# kbd.net
KiCad netlist of a schematic drawn in Altium Designer
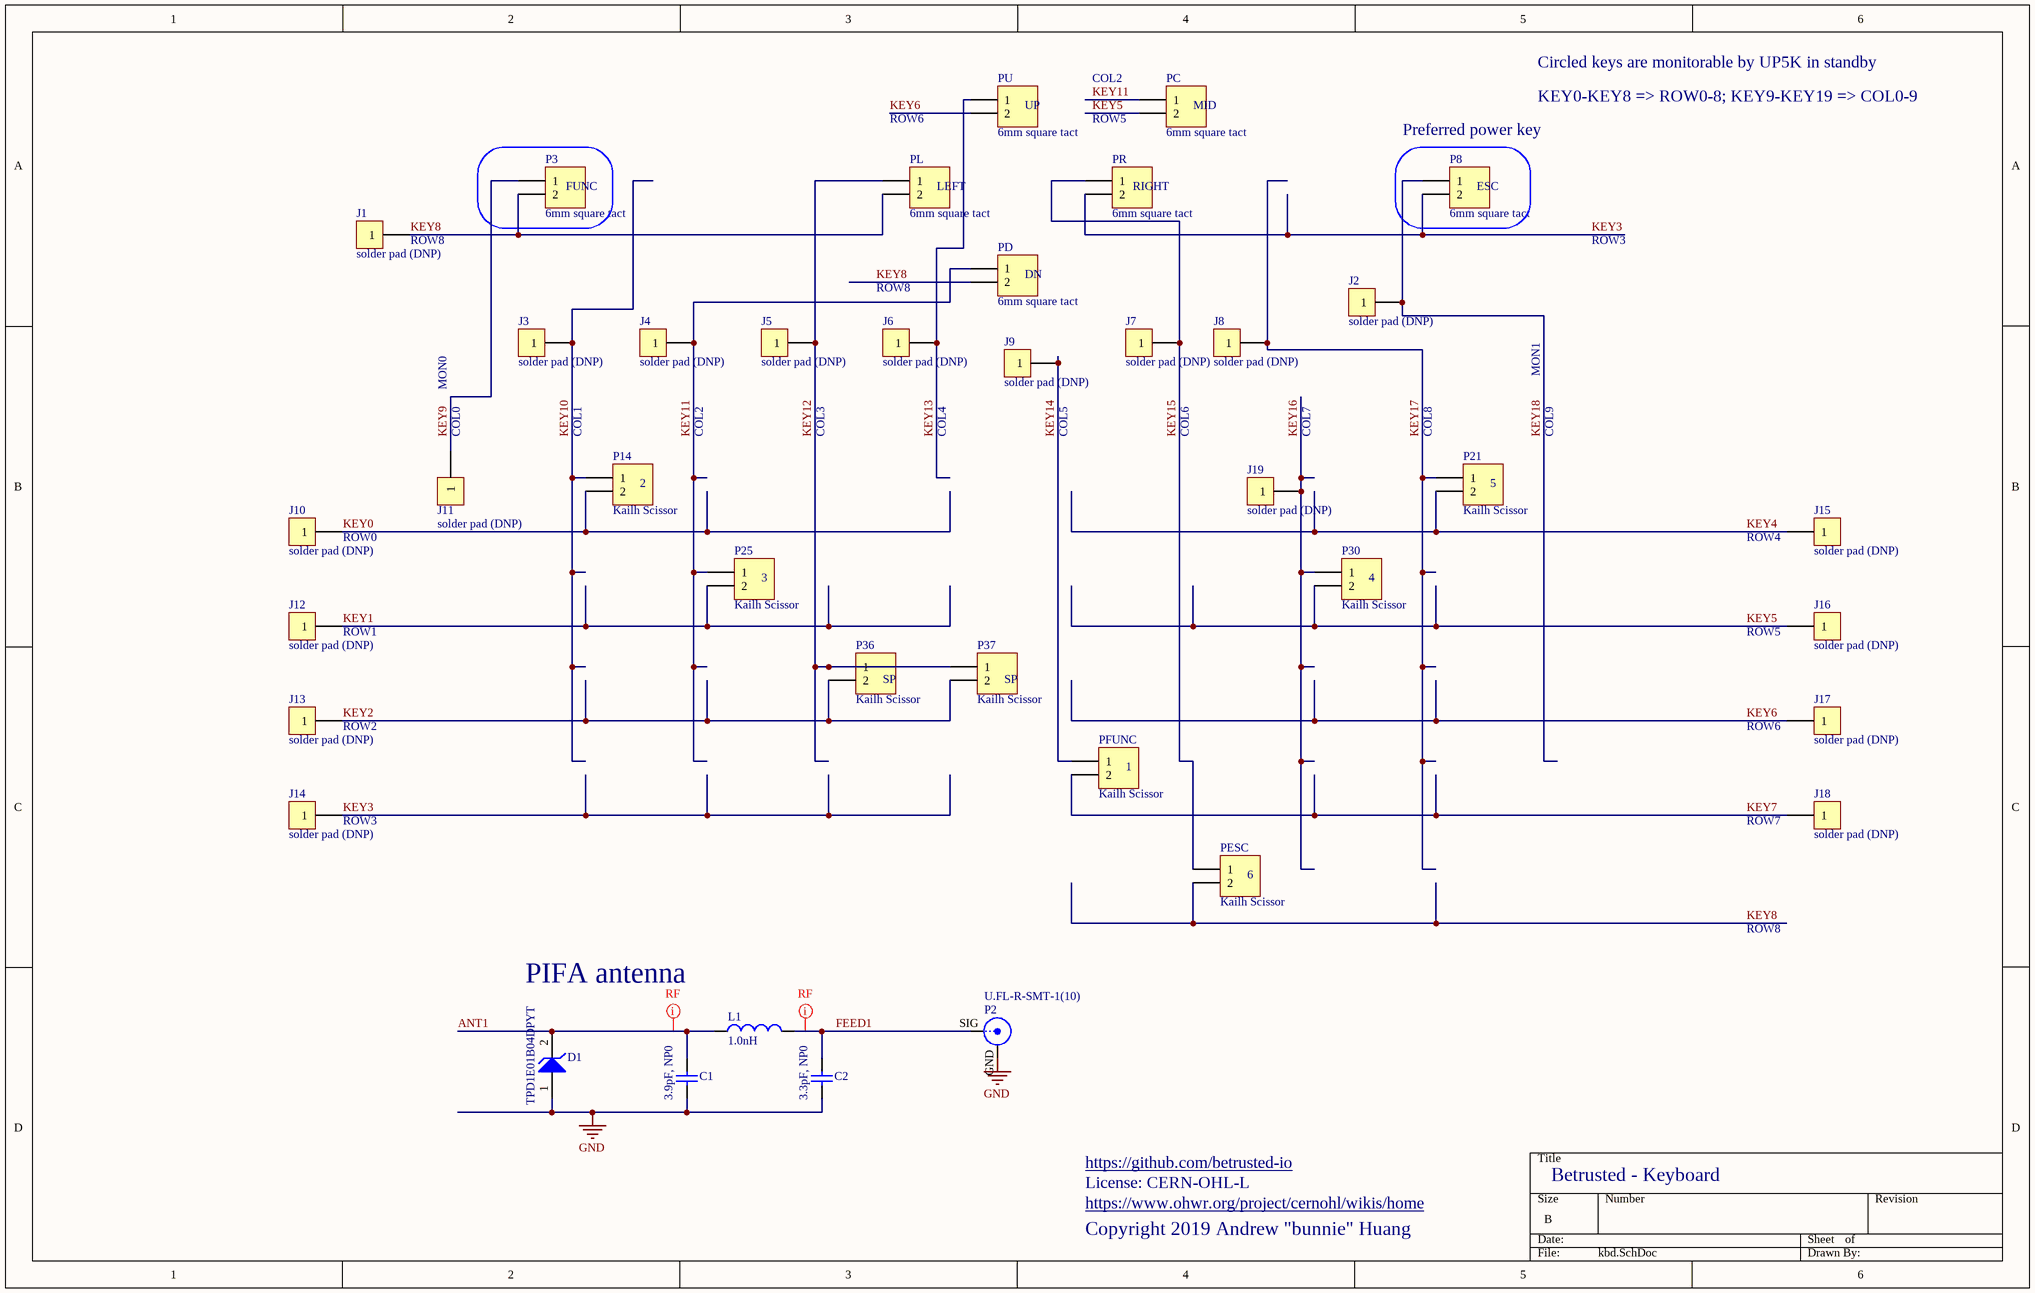
[diagram p0: kbd.SchDoc]

(export (version "E")
  (design (tool "Eeschema 10.0.6"))
  (components
    (comp (ref "C1")
      (value "3.9pF, NP0")
      (footprint "B_CAP0402")
      (description "Capacitor (Semiconductor SIM Model)")
      (fields (field (name "MPN") "CL05C3R9CB5NNNC"))
      (libsource (lib "Miscellaneous Devices") (part "Cap Semi"))
    )
    (comp (ref "C2")
      (value "3.3pF, NP0")
      (footprint "B_CAP0402")
      (description "Capacitor (Semiconductor SIM Model)")
      (fields (field (name "MPN") "GRM1555C1H3R3CA01D"))
      (libsource (lib "Miscellaneous Devices") (part "Cap Semi"))
    )
    (comp (ref "D1")
      (value "TPD1E01B04DPYT")
      (footprint "TI_PX1SON-N2")
      (description "CPDUR24V")
      (fields (field (name "PUBLISHER") "Altium Limited"))
      (libsource (lib "Miscellaneous Devices") (part "D Zener"))
    )
    (comp (ref "J1")
      (value "solder pad (DNP)")
      (footprint "TP_1.5x1.5_SMT")
      (description "Connector")
      (fields (field (name "MPN") "DNP"))
      (libsource (lib "") (part "CON1_2"))
    )
    (comp (ref "J2")
      (value "solder pad (DNP)")
      (footprint "TP_1.5x1.5_SMT")
      (description "Connector")
      (fields (field (name "MPN") "DNP"))
      (libsource (lib "") (part "CON1_2"))
    )
    (comp (ref "J3")
      (value "solder pad (DNP)")
      (footprint "TP_1.5x1.5_SMT")
      (description "Connector")
      (fields (field (name "MPN") "DNP"))
      (libsource (lib "") (part "CON1_2"))
    )
    (comp (ref "J4")
      (value "solder pad (DNP)")
      (footprint "TP_1.5x1.5_SMT")
      (description "Connector")
      (fields (field (name "MPN") "DNP"))
      (libsource (lib "") (part "CON1_2"))
    )
    (comp (ref "J5")
      (value "solder pad (DNP)")
      (footprint "TP_1.5x1.5_SMT")
      (description "Connector")
      (fields (field (name "MPN") "DNP"))
      (libsource (lib "") (part "CON1_2"))
    )
    (comp (ref "J6")
      (value "solder pad (DNP)")
      (footprint "TP_1.5x1.5_SMT")
      (description "Connector")
      (fields (field (name "MPN") "DNP"))
      (libsource (lib "") (part "CON1_2"))
    )
    (comp (ref "J7")
      (value "solder pad (DNP)")
      (footprint "TP_1.5x1.5_SMT")
      (description "Connector")
      (fields (field (name "MPN") "DNP"))
      (libsource (lib "") (part "CON1_2"))
    )
    (comp (ref "J8")
      (value "solder pad (DNP)")
      (footprint "TP_1.5x1.5_SMT")
      (description "Connector")
      (fields (field (name "MPN") "DNP"))
      (libsource (lib "") (part "CON1_2"))
    )
    (comp (ref "J9")
      (value "solder pad (DNP)")
      (footprint "TP_1.5x1.5_SMT")
      (description "Connector")
      (fields (field (name "MPN") "DNP"))
      (libsource (lib "") (part "CON1_2"))
    )
    (comp (ref "J10")
      (value "solder pad (DNP)")
      (footprint "TP_1.5x1.5_SMT")
      (description "Connector")
      (fields (field (name "MPN") "DNP"))
      (libsource (lib "") (part "CON1_2"))
    )
    (comp (ref "J11")
      (value "solder pad (DNP)")
      (footprint "TP_1.5x1.5_SMT")
      (description "Connector")
      (fields (field (name "MPN") "DNP"))
      (libsource (lib "") (part "CON1_1"))
    )
    (comp (ref "J12")
      (value "solder pad (DNP)")
      (footprint "TP_1.5x1.5_SMT")
      (description "Connector")
      (fields (field (name "MPN") "DNP"))
      (libsource (lib "") (part "CON1_2"))
    )
    (comp (ref "J13")
      (value "solder pad (DNP)")
      (footprint "TP_1.5x1.5_SMT")
      (description "Connector")
      (fields (field (name "MPN") "DNP"))
      (libsource (lib "") (part "CON1_2"))
    )
    (comp (ref "J14")
      (value "solder pad (DNP)")
      (footprint "TP_1.5x1.5_SMT")
      (description "Connector")
      (fields (field (name "MPN") "DNP"))
      (libsource (lib "") (part "CON1_2"))
    )
    (comp (ref "J15")
      (value "solder pad (DNP)")
      (footprint "TP_1.5x1.5_SMT")
      (description "Connector")
      (fields (field (name "MPN") "DNP"))
      (libsource (lib "*") (part "CON1"))
    )
    (comp (ref "J16")
      (value "solder pad (DNP)")
      (footprint "TP_1.5x1.5_SMT")
      (description "Connector")
      (fields (field (name "MPN") "DNP"))
      (libsource (lib "*") (part "CON1"))
    )
    (comp (ref "J17")
      (value "solder pad (DNP)")
      (footprint "TP_1.5x1.5_SMT")
      (description "Connector")
      (fields (field (name "MPN") "DNP"))
      (libsource (lib "*") (part "CON1"))
    )
    (comp (ref "J18")
      (value "solder pad (DNP)")
      (footprint "TP_1.5x1.5_SMT")
      (description "Connector")
      (fields (field (name "MPN") "DNP"))
      (libsource (lib "*") (part "CON1"))
    )
    (comp (ref "J19")
      (value "solder pad (DNP)")
      (footprint "TP_1.5x1.5_SMT")
      (description "Connector")
      (fields (field (name "MPN") "DNP"))
      (libsource (lib "") (part "CON1_2"))
    )
    (comp (ref "L1")
      (value "1.0nH")
      (footprint "B_IND0402")
      (description "Inductor")
      (fields (field (name "MPN") "LQG15HS1N0S02D") (field (name "PUBLISHER") "Altium Limited"))
      (libsource (lib "Miscellaneous Devices") (part "Inductor"))
    )
    (comp (ref "P2")
      (value "U.FL-R-SMT-1(10)")
      (footprint "HRS_U.FL")
      (description "BNC Elbow Connector")
      (fields (field (name "MPN") "P1163-0140R") (field (name "PUBLISHER") "Altium Limited"))
      (libsource (lib "Miscellaneous Connectors") (part "BNC"))
    )
    (comp (ref "P3")
      (value "6mm square tact")
      (footprint "PANASONIC_EVPAS")
      (description "Header, 2-Pin")
      (fields (field (name "MPN") "EVP-ASAC1A") (field (name "PUBLISHER") "Altium Limited"))
      (libsource (lib "Miscellaneous Connectors") (part "Header 2"))
    )
    (comp (ref "P8")
      (value "6mm square tact")
      (footprint "PANASONIC_EVPAS")
      (description "Header, 2-Pin")
      (fields (field (name "MPN") "EVP-ASAC1A") (field (name "PUBLISHER") "Altium Limited"))
      (libsource (lib "Miscellaneous Connectors") (part "Header 2"))
    )
    (comp (ref "P14")
      (value "Kailh Scissor")
      (footprint "KAILH_CPG142501D03")
      (description "Header, 2-Pin")
      (fields (field (name "MPN") "CPG142501D03") (field (name "PUBLISHER") "Altium Limited"))
      (libsource (lib "Miscellaneous Connectors") (part "Header 2"))
    )
    (comp (ref "P21")
      (value "Kailh Scissor")
      (footprint "KAILH_CPG142501D03")
      (description "Header, 2-Pin")
      (fields (field (name "MPN") "CPG142501D03") (field (name "PUBLISHER") "Altium Limited"))
      (libsource (lib "Miscellaneous Connectors") (part "Header 2"))
    )
    (comp (ref "P25")
      (value "Kailh Scissor")
      (footprint "KAILH_CPG142501D03")
      (description "Header, 2-Pin")
      (fields (field (name "MPN") "CPG142501D03") (field (name "PUBLISHER") "Altium Limited"))
      (libsource (lib "Miscellaneous Connectors") (part "Header 2"))
    )
    (comp (ref "P30")
      (value "Kailh Scissor")
      (footprint "KAILH_CPG142501D03")
      (description "Header, 2-Pin")
      (fields (field (name "MPN") "CPG142501D03") (field (name "PUBLISHER") "Altium Limited"))
      (libsource (lib "Miscellaneous Connectors") (part "Header 2"))
    )
    (comp (ref "P36")
      (value "Kailh Scissor")
      (footprint "KAILH_CPG142501D03")
      (description "Header, 2-Pin")
      (fields (field (name "MPN") "CPG142501D03") (field (name "PUBLISHER") "Altium Limited"))
      (libsource (lib "Miscellaneous Connectors") (part "Header 2"))
    )
    (comp (ref "P37")
      (value "Kailh Scissor")
      (footprint "KAILH_CPG142501D03")
      (description "Header, 2-Pin")
      (fields (field (name "MPN") "CPG142501D03") (field (name "PUBLISHER") "Altium Limited"))
      (libsource (lib "Miscellaneous Connectors") (part "Header 2"))
    )
    (comp (ref "PC")
      (value "6mm square tact")
      (footprint "PANASONIC_EVPAS")
      (description "Header, 2-Pin")
      (fields (field (name "MPN") "EVP-ASAC1A") (field (name "PUBLISHER") "Altium Limited"))
      (libsource (lib "Miscellaneous Connectors") (part "Header 2"))
    )
    (comp (ref "PD")
      (value "6mm square tact")
      (footprint "PANASONIC_EVPAS")
      (description "Header, 2-Pin")
      (fields (field (name "MPN") "EVP-ASAC1A") (field (name "PUBLISHER") "Altium Limited"))
      (libsource (lib "Miscellaneous Connectors") (part "Header 2"))
    )
    (comp (ref "PESC")
      (value "Kailh Scissor")
      (footprint "KAILH_CPG142501D03")
      (description "Header, 2-Pin")
      (fields (field (name "MPN") "CPG142501D03") (field (name "PUBLISHER") "Altium Limited"))
      (libsource (lib "Miscellaneous Connectors") (part "Header 2"))
    )
    (comp (ref "PFUNC")
      (value "Kailh Scissor")
      (footprint "KAILH_CPG142501D03")
      (description "Header, 2-Pin")
      (fields (field (name "MPN") "CPG142501D03") (field (name "PUBLISHER") "Altium Limited"))
      (libsource (lib "Miscellaneous Connectors") (part "Header 2"))
    )
    (comp (ref "PL")
      (value "6mm square tact")
      (footprint "PANASONIC_EVPAS")
      (description "Header, 2-Pin")
      (fields (field (name "MPN") "EVP-ASAC1A") (field (name "PUBLISHER") "Altium Limited"))
      (libsource (lib "Miscellaneous Connectors") (part "Header 2"))
    )
    (comp (ref "PR")
      (value "6mm square tact")
      (footprint "PANASONIC_EVPAS")
      (description "Header, 2-Pin")
      (fields (field (name "MPN") "EVP-ASAC1A") (field (name "PUBLISHER") "Altium Limited"))
      (libsource (lib "Miscellaneous Connectors") (part "Header 2"))
    )
    (comp (ref "PU")
      (value "6mm square tact")
      (footprint "PANASONIC_EVPAS")
      (description "Header, 2-Pin")
      (fields (field (name "MPN") "EVP-ASAC1A") (field (name "PUBLISHER") "Altium Limited"))
      (libsource (lib "Miscellaneous Connectors") (part "Header 2"))
    )
  )
  (nets
    (net (code "1") (name "/ANT1") (class "Default")
      (node (ref "C1") (pin "1") (pinfunction "1_1") (pintype "passive"))
      (node (ref "D1") (pin "2") (pinfunction "K_2") (pintype "passive"))
      (node (ref "L1") (pin "1") (pinfunction "1_1") (pintype "passive"))
    )
    (net (code "2") (name "/FEED1") (class "Default")
      (node (ref "C2") (pin "1") (pinfunction "1_1") (pintype "passive"))
      (node (ref "L1") (pin "2") (pinfunction "2_2") (pintype "passive"))
      (node (ref "P2") (pin "SIG") (pinfunction "X_SIG") (pintype "passive"))
    )
    (net (code "3") (name "/KEY0") (class "Default")
      (node (ref "J10") (pin "1") (pinfunction "1_1") (pintype "passive"))
      (node (ref "P14") (pin "2") (pinfunction "2_2") (pintype "passive"))
    )
    (net (code "4") (name "/KEY1") (class "Default")
      (node (ref "J12") (pin "1") (pinfunction "1_1") (pintype "passive"))
      (node (ref "P25") (pin "2") (pinfunction "2_2") (pintype "passive"))
    )
    (net (code "5") (name "/KEY2") (class "Default")
      (node (ref "J13") (pin "1") (pinfunction "1_1") (pintype "passive"))
      (node (ref "P36") (pin "2") (pinfunction "2_2") (pintype "passive"))
      (node (ref "P37") (pin "2") (pinfunction "2_2") (pintype "passive"))
    )
    (net (code "6") (name "/KEY3") (class "Default")
      (node (ref "J14") (pin "1") (pinfunction "1_1") (pintype "passive"))
      (node (ref "P8") (pin "2") (pinfunction "2_2") (pintype "passive"))
      (node (ref "PR") (pin "2") (pinfunction "2_2") (pintype "passive"))
    )
    (net (code "7") (name "/KEY4") (class "Default")
      (node (ref "J15") (pin "1") (pinfunction "1_1") (pintype "passive"))
      (node (ref "P21") (pin "2") (pinfunction "2_2") (pintype "passive"))
    )
    (net (code "8") (name "/KEY5") (class "Default")
      (node (ref "J16") (pin "1") (pinfunction "1_1") (pintype "passive"))
      (node (ref "P30") (pin "2") (pinfunction "2_2") (pintype "passive"))
      (node (ref "PC") (pin "2") (pinfunction "2_2") (pintype "passive"))
    )
    (net (code "9") (name "/KEY6") (class "Default")
      (node (ref "J17") (pin "1") (pinfunction "1_1") (pintype "passive"))
      (node (ref "PU") (pin "2") (pinfunction "2_2") (pintype "passive"))
    )
    (net (code "10") (name "/KEY7") (class "Default")
      (node (ref "J18") (pin "1") (pinfunction "1_1") (pintype "passive"))
      (node (ref "PFUNC") (pin "2") (pinfunction "2_2") (pintype "passive"))
    )
    (net (code "11") (name "/KEY8") (class "Default")
      (node (ref "J1") (pin "1") (pinfunction "1_1") (pintype "passive"))
      (node (ref "P3") (pin "2") (pinfunction "2_2") (pintype "passive"))
      (node (ref "PD") (pin "2") (pinfunction "2_2") (pintype "passive"))
      (node (ref "PESC") (pin "2") (pinfunction "2_2") (pintype "passive"))
      (node (ref "PL") (pin "2") (pinfunction "2_2") (pintype "passive"))
    )
    (net (code "12") (name "/KEY9") (class "Default")
      (node (ref "J11") (pin "1") (pinfunction "1_1") (pintype "passive"))
      (node (ref "P3") (pin "1") (pinfunction "1_1") (pintype "passive"))
    )
    (net (code "13") (name "/KEY10") (class "Default")
      (node (ref "J3") (pin "1") (pinfunction "1_1") (pintype "passive"))
      (node (ref "P14") (pin "1") (pinfunction "1_1") (pintype "passive"))
    )
    (net (code "14") (name "/KEY11") (class "Default")
      (node (ref "J4") (pin "1") (pinfunction "1_1") (pintype "passive"))
      (node (ref "P25") (pin "1") (pinfunction "1_1") (pintype "passive"))
      (node (ref "PC") (pin "1") (pinfunction "1_1") (pintype "passive"))
      (node (ref "PD") (pin "1") (pinfunction "1_1") (pintype "passive"))
    )
    (net (code "15") (name "/KEY12") (class "Default")
      (node (ref "J5") (pin "1") (pinfunction "1_1") (pintype "passive"))
      (node (ref "P36") (pin "1") (pinfunction "1_1") (pintype "passive"))
      (node (ref "P37") (pin "1") (pinfunction "1_1") (pintype "passive"))
      (node (ref "PL") (pin "1") (pinfunction "1_1") (pintype "passive"))
    )
    (net (code "16") (name "/KEY13") (class "Default")
      (node (ref "J6") (pin "1") (pinfunction "1_1") (pintype "passive"))
      (node (ref "PU") (pin "1") (pinfunction "1_1") (pintype "passive"))
    )
    (net (code "17") (name "/KEY14") (class "Default")
      (node (ref "J9") (pin "1") (pinfunction "1_1") (pintype "passive"))
      (node (ref "PFUNC") (pin "1") (pinfunction "1_1") (pintype "passive"))
    )
    (net (code "18") (name "/KEY15") (class "Default")
      (node (ref "J7") (pin "1") (pinfunction "1_1") (pintype "passive"))
      (node (ref "PESC") (pin "1") (pinfunction "1_1") (pintype "passive"))
      (node (ref "PR") (pin "1") (pinfunction "1_1") (pintype "passive"))
    )
    (net (code "19") (name "/KEY16") (class "Default")
      (node (ref "J19") (pin "1") (pinfunction "1_1") (pintype "passive"))
      (node (ref "P30") (pin "1") (pinfunction "1_1") (pintype "passive"))
    )
    (net (code "20") (name "/KEY17") (class "Default")
      (node (ref "J8") (pin "1") (pinfunction "1_1") (pintype "passive"))
      (node (ref "P21") (pin "1") (pinfunction "1_1") (pintype "passive"))
    )
    (net (code "21") (name "/KEY18") (class "Default")
      (node (ref "J2") (pin "1") (pinfunction "1_1") (pintype "passive"))
      (node (ref "P8") (pin "1") (pinfunction "1_1") (pintype "passive"))
    )
    (net (code "22") (name "GND") (class "Default")
      (node (ref "C1") (pin "2") (pinfunction "2_2") (pintype "passive"))
      (node (ref "C2") (pin "2") (pinfunction "2_2") (pintype "passive"))
      (node (ref "D1") (pin "1") (pinfunction "A_1") (pintype "passive"))
      (node (ref "P2") (pin "GND") (pinfunction "Y_GND") (pintype "passive"))
    )
  )
)
